# HDC100X-Breakout_v11.net
KiCad netlist of a schematic drawn in EAGLE
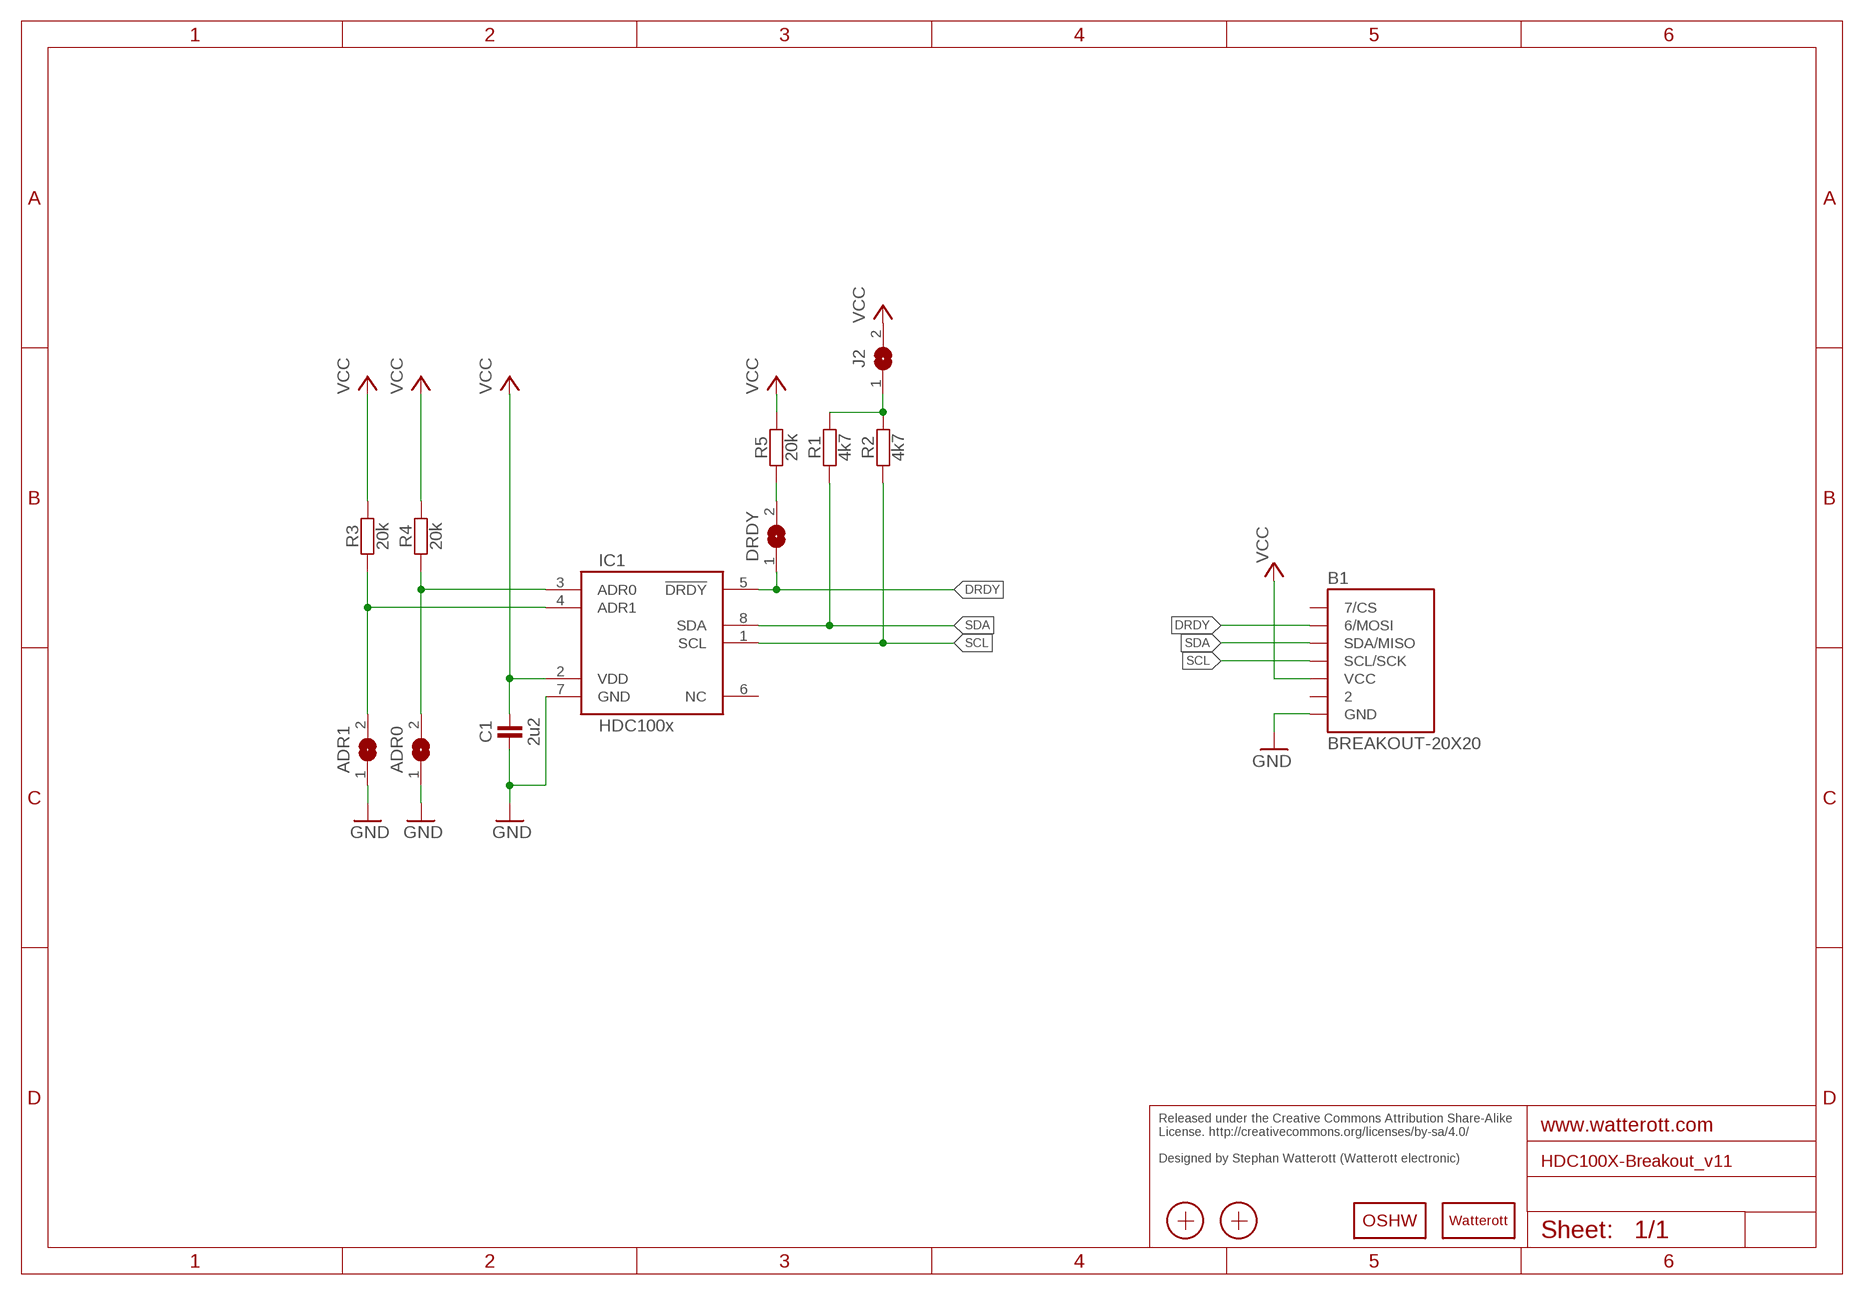
[diagram p0: schematic, sheet 1]

(export (version "E")
  (design (tool "Eeschema 10.0.6"))
  (components
    (comp (ref "ADR0")
      (value "JUMPER2-0402")
      (footprint "eagle-import:JUMPER2-0402")
      (libsource (lib "eagle-import") (part "JUMPER2-0402"))
    )
    (comp (ref "ADR1")
      (value "JUMPER2-0402")
      (footprint "eagle-import:JUMPER2-0402")
      (libsource (lib "eagle-import") (part "JUMPER2-0402"))
    )
    (comp (ref "B1")
      (value "BREAKOUT-20X20")
      (footprint "eagle-import:BREAKOUT-20X20")
      (libsource (lib "eagle-import") (part "BREAKOUT-20X20"))
    )
    (comp (ref "C1")
      (value "2u2")
      (footprint "eagle-import:R0402")
      (libsource (lib "eagle-import") (part "CAPACITOR-C0402"))
    )
    (comp (ref "DRDY")
      (value "JUMPER2-0402")
      (footprint "eagle-import:JUMPER2-0402")
      (libsource (lib "eagle-import") (part "JUMPER2-0402"))
    )
    (comp (ref "IC1")
      (value "HDC100x")
      (footprint "eagle-import:WLCSP")
      (libsource (lib "eagle-import") (part "HDC1008"))
    )
    (comp (ref "J2")
      (value "JUMPER2-0603")
      (footprint "eagle-import:JUMPER2-0603")
      (libsource (lib "eagle-import") (part "JUMPER2-0603"))
    )
    (comp (ref "LOGO2")
      (value "OSHW_LOGOX0070")
      (footprint "eagle-import:OSHW_6X70")
      (libsource (lib "eagle-import") (part "OSHW_LOGOX0070"))
    )
    (comp (ref "LOGO3")
      (value "LOGO-S_PLACE_M")
      (footprint "eagle-import:SPARK_TPLACE_M")
      (libsource (lib "eagle-import") (part "LOGO-S_PLACE_M"))
    )
    (comp (ref "R1")
      (value "4k7")
      (footprint "eagle-import:R0402")
      (libsource (lib "eagle-import") (part "RESISTOR-R0402"))
    )
    (comp (ref "R2")
      (value "4k7")
      (footprint "eagle-import:R0402")
      (libsource (lib "eagle-import") (part "RESISTOR-R0402"))
    )
    (comp (ref "R3")
      (value "20k")
      (footprint "eagle-import:R0402")
      (libsource (lib "eagle-import") (part "RESISTOR-R0402"))
    )
    (comp (ref "R4")
      (value "20k")
      (footprint "eagle-import:R0402")
      (libsource (lib "eagle-import") (part "RESISTOR-R0402"))
    )
    (comp (ref "R5")
      (value "20k")
      (footprint "eagle-import:R0402")
      (libsource (lib "eagle-import") (part "RESISTOR-R0402"))
    )
    (comp (ref "X1")
      (value "PASSER-07")
      (footprint "eagle-import:PASSER_07MM")
      (libsource (lib "eagle-import") (part "PASSER-07"))
    )
    (comp (ref "X2")
      (value "PASSER-07")
      (footprint "eagle-import:PASSER_07MM")
      (libsource (lib "eagle-import") (part "PASSER-07"))
    )
  )
  (nets
    (net (code "1") (name "DRDY") (class "Default")
      (node (ref "B1") (pin "MOSI") (pinfunction "6/MOSI_MOSI") (pintype "bidirectional"))
      (node (ref "DRDY") (pin "1") (pinfunction "1_1") (pintype "passive"))
      (node (ref "IC1") (pin "5") (pinfunction "~{DRDY}_5") (pintype "output"))
    )
    (net (code "2") (name "GND") (class "Default")
      (node (ref "ADR0") (pin "1") (pinfunction "1_1") (pintype "passive"))
      (node (ref "ADR1") (pin "1") (pinfunction "1_1") (pintype "passive"))
      (node (ref "B1") (pin "GND") (pinfunction "GND_GND") (pintype "power_in"))
      (node (ref "C1") (pin "1") (pinfunction "1_1") (pintype "passive"))
      (node (ref "IC1") (pin "7") (pinfunction "GND_7") (pintype "power_in"))
    )
    (net (code "3") (name "Net-(DRDY-Pad2)") (class "Default")
      (node (ref "DRDY") (pin "2") (pinfunction "2_2") (pintype "passive"))
      (node (ref "R5") (pin "1") (pinfunction "1_1") (pintype "passive"))
    )
    (net (code "4") (name "Net-(IC1-ADR0)") (class "Default")
      (node (ref "ADR0") (pin "2") (pinfunction "2_2") (pintype "passive"))
      (node (ref "IC1") (pin "3") (pinfunction "ADR0_3") (pintype "input"))
      (node (ref "R4") (pin "1") (pinfunction "1_1") (pintype "passive"))
    )
    (net (code "5") (name "Net-(IC1-ADR1)") (class "Default")
      (node (ref "ADR1") (pin "2") (pinfunction "2_2") (pintype "passive"))
      (node (ref "IC1") (pin "4") (pinfunction "ADR1_4") (pintype "input"))
      (node (ref "R3") (pin "1") (pinfunction "1_1") (pintype "passive"))
    )
    (net (code "6") (name "Net-(J2-Pad1)") (class "Default")
      (node (ref "J2") (pin "1") (pinfunction "1_1") (pintype "passive"))
      (node (ref "R1") (pin "2") (pinfunction "2_2") (pintype "passive"))
      (node (ref "R2") (pin "2") (pinfunction "2_2") (pintype "passive"))
    )
    (net (code "7") (name "SCL") (class "Default")
      (node (ref "B1") (pin "SCL/SCK") (pinfunction "SCL/SCK_SCL/SCK") (pintype "bidirectional"))
      (node (ref "IC1") (pin "1") (pinfunction "SCL_1") (pintype "input"))
      (node (ref "R2") (pin "1") (pinfunction "1_1") (pintype "passive"))
    )
    (net (code "8") (name "SDA") (class "Default")
      (node (ref "B1") (pin "SDA/MISO") (pinfunction "SDA/MISO_SDA/MISO") (pintype "bidirectional"))
      (node (ref "IC1") (pin "8") (pinfunction "SDA_8") (pintype "bidirectional"))
      (node (ref "R1") (pin "1") (pinfunction "1_1") (pintype "passive"))
    )
    (net (code "9") (name "VCC") (class "Default")
      (node (ref "B1") (pin "VCC") (pinfunction "VCC_VCC") (pintype "power_in"))
      (node (ref "C1") (pin "2") (pinfunction "2_2") (pintype "passive"))
      (node (ref "IC1") (pin "2") (pinfunction "VDD_2") (pintype "power_in"))
      (node (ref "J2") (pin "2") (pinfunction "2_2") (pintype "passive"))
      (node (ref "R3") (pin "2") (pinfunction "2_2") (pintype "passive"))
      (node (ref "R4") (pin "2") (pinfunction "2_2") (pintype "passive"))
      (node (ref "R5") (pin "2") (pinfunction "2_2") (pintype "passive"))
    )
    (net (code "10") (name "unconnected-(B1-7{slash}CS-PadCS)") (class "Default")
      (node (ref "B1") (pin "CS") (pinfunction "7/CS_CS") (pintype "bidirectional"))
    )
    (net (code "11") (name "unconnected-(B1-Pad2)") (class "Default")
      (node (ref "B1") (pin "2") (pinfunction "2_2") (pintype "bidirectional"))
    )
    (net (code "12") (name "unconnected-(IC1-NC-Pad6)") (class "Default")
      (node (ref "IC1") (pin "6") (pinfunction "NC_6") (pintype "no_connect"))
    )
  )
)
